# ZSLC.net
KiCad netlist of a schematic drawn in EAGLE
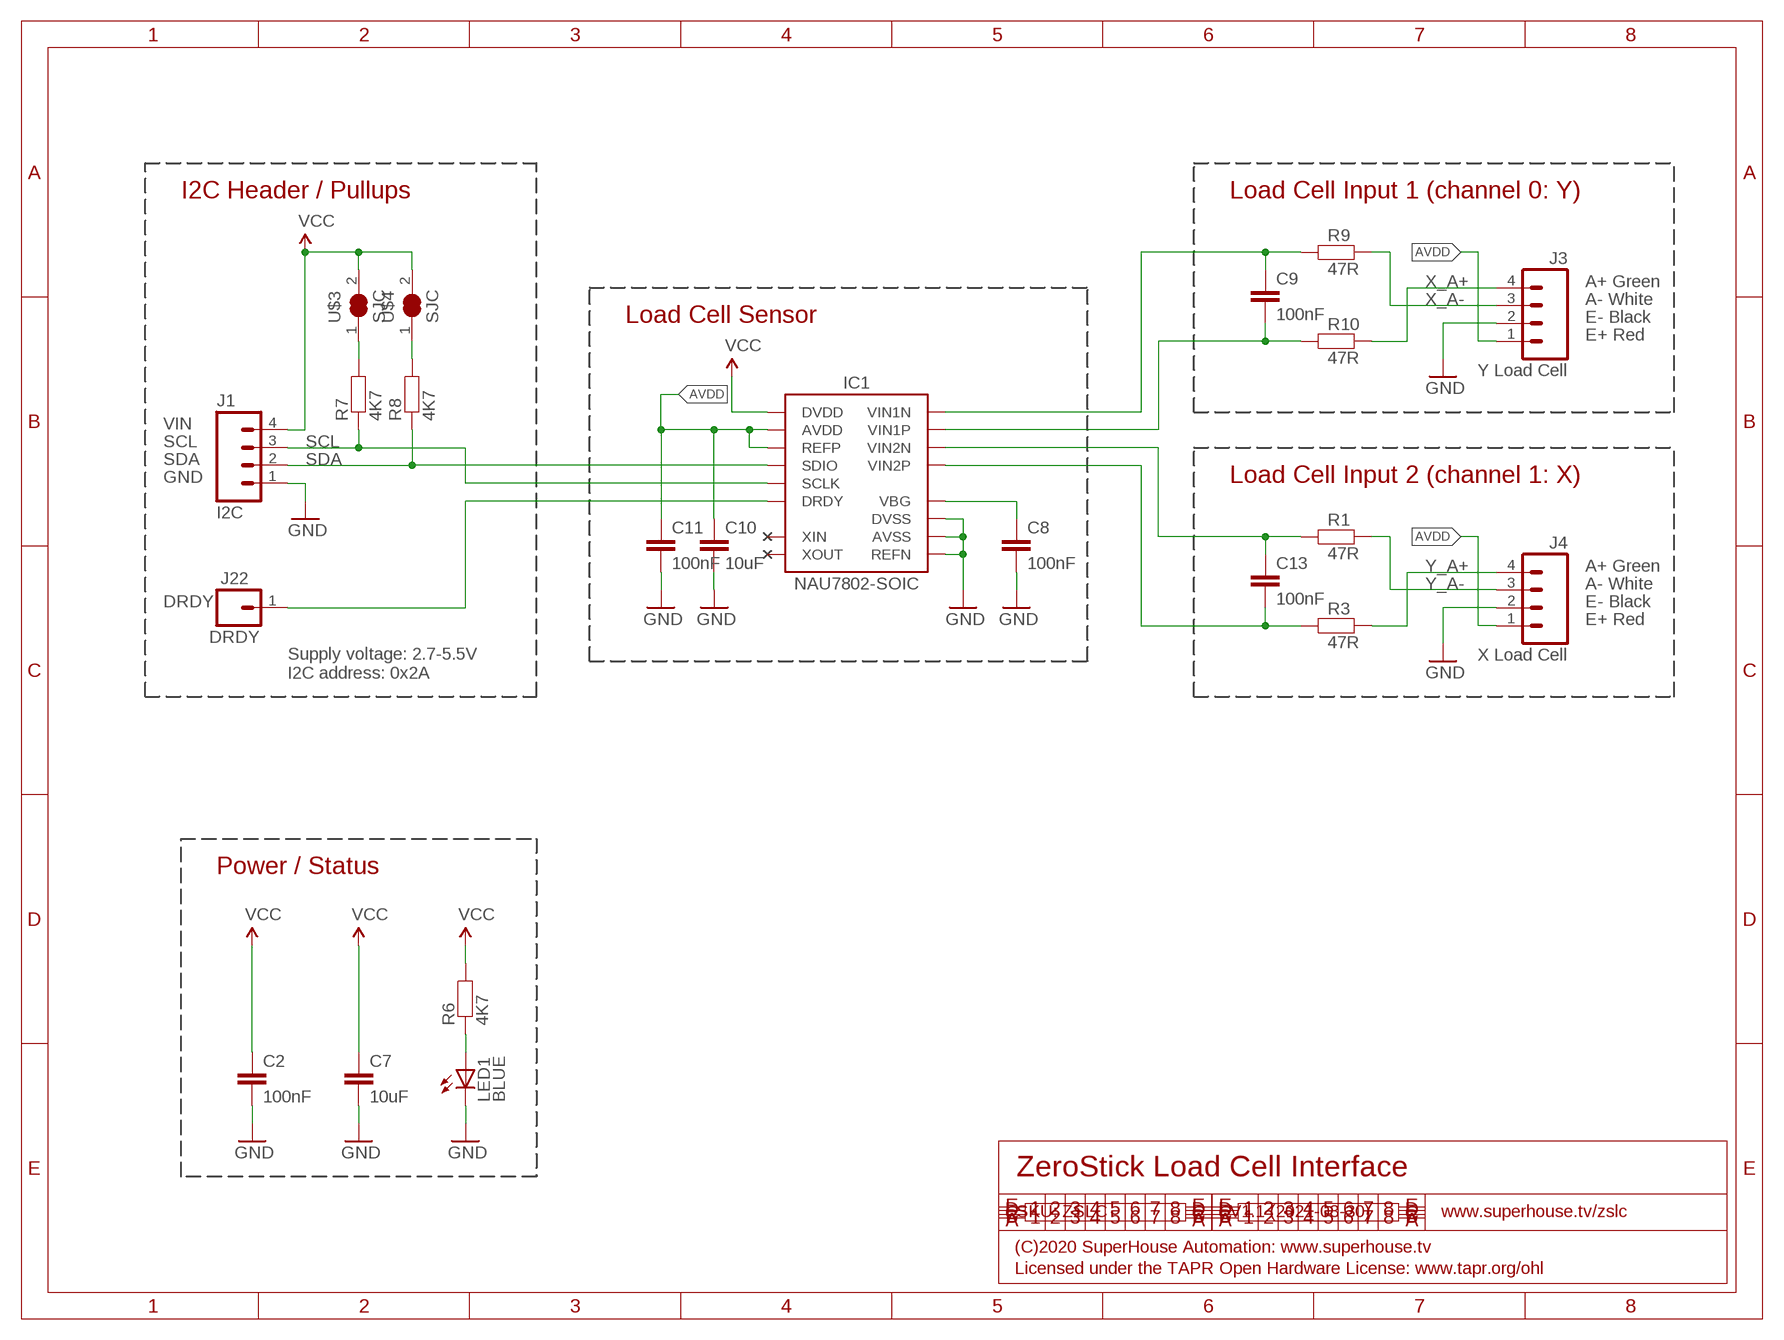
[diagram p0: schematic, sheet 1]

(export (version "E")
  (design (tool "Eeschema 10.0.6"))
  (components
    (comp (ref "C2")
      (value "100nF")
      (footprint "eagle-import:C0603")
      (libsource (lib "eagle-import") (part "CAP0603"))
    )
    (comp (ref "C7")
      (value "10uF")
      (footprint "eagle-import:C0805")
      (libsource (lib "eagle-import") (part "CAP0805"))
    )
    (comp (ref "C8")
      (value "100nF")
      (footprint "eagle-import:C0603")
      (libsource (lib "eagle-import") (part "CAP0603"))
    )
    (comp (ref "C9")
      (value "100nF")
      (footprint "eagle-import:C0603")
      (libsource (lib "eagle-import") (part "CAP0603"))
    )
    (comp (ref "C10")
      (value "10uF")
      (footprint "eagle-import:C0805")
      (libsource (lib "eagle-import") (part "CAP0805"))
    )
    (comp (ref "C11")
      (value "100nF")
      (footprint "eagle-import:C0603")
      (libsource (lib "eagle-import") (part "CAP0603"))
    )
    (comp (ref "C13")
      (value "100nF")
      (footprint "eagle-import:C0603")
      (libsource (lib "eagle-import") (part "CAP0603"))
    )
    (comp (ref "IC1")
      (value "NAU7802-SOIC")
      (footprint "eagle-import:SO16")
      (libsource (lib "eagle-import") (part "NAU7802-SOIC"))
    )
    (comp (ref "J1")
      (value "I2C")
      (footprint "eagle-import:1X04")
      (libsource (lib "eagle-import") (part "M04-PLAIN"))
    )
    (comp (ref "J3")
      (value "Y Load Cell")
      (footprint "eagle-import:1X04-1.27-PLAIN")
      (libsource (lib "eagle-import") (part "M04-1.27-PLAIN"))
    )
    (comp (ref "J4")
      (value "X Load Cell")
      (footprint "eagle-import:1X04-1.27-PLAIN")
      (libsource (lib "eagle-import") (part "M04-1.27-PLAIN"))
    )
    (comp (ref "J22")
      (value "DRDY")
      (footprint "eagle-import:1X01")
      (libsource (lib "eagle-import") (part "M01-PLAIN"))
    )
    (comp (ref "LED1")
      (value "BLUE")
      (footprint "eagle-import:LED-0603")
      (libsource (lib "eagle-import") (part "LED0603"))
    )
    (comp (ref "R1")
      (value "47R")
      (footprint "eagle-import:R0603")
      (libsource (lib "eagle-import") (part "RESISTOR0603"))
    )
    (comp (ref "R3")
      (value "47R")
      (footprint "eagle-import:R0603")
      (libsource (lib "eagle-import") (part "RESISTOR0603"))
    )
    (comp (ref "R6")
      (value "4K7")
      (footprint "eagle-import:R0603")
      (libsource (lib "eagle-import") (part "RESISTOR0603"))
    )
    (comp (ref "R7")
      (value "4K7")
      (footprint "eagle-import:R0603")
      (libsource (lib "eagle-import") (part "RESISTOR0603"))
    )
    (comp (ref "R8")
      (value "4K7")
      (footprint "eagle-import:R0603")
      (libsource (lib "eagle-import") (part "RESISTOR0603"))
    )
    (comp (ref "R9")
      (value "47R")
      (footprint "eagle-import:R0603")
      (libsource (lib "eagle-import") (part "RESISTOR0603"))
    )
    (comp (ref "R10")
      (value "47R")
      (footprint "eagle-import:R0603")
      (libsource (lib "eagle-import") (part "RESISTOR0603"))
    )
    (comp (ref "U$3")
      (value "SJC")
      (footprint "eagle-import:SJC")
      (libsource (lib "eagle-import") (part "SJC-NORMAL"))
    )
    (comp (ref "U$4")
      (value "SJC")
      (footprint "eagle-import:SJC")
      (libsource (lib "eagle-import") (part "SJC-NORMAL"))
    )
  )
  (nets
    (net (code "1") (name "/SCL") (class "Default")
      (node (ref "IC1") (pin "13") (pinfunction "SCLK_13") (pintype "bidirectional"))
      (node (ref "J1") (pin "3") (pinfunction "3_3") (pintype "passive"))
      (node (ref "R7") (pin "1") (pinfunction "1_1") (pintype "passive"))
    )
    (net (code "2") (name "/SDA") (class "Default")
      (node (ref "IC1") (pin "14") (pinfunction "SDIO_14") (pintype "bidirectional"))
      (node (ref "J1") (pin "2") (pinfunction "2_2") (pintype "passive"))
      (node (ref "R8") (pin "1") (pinfunction "1_1") (pintype "passive"))
    )
    (net (code "3") (name "/X_A+") (class "Default")
      (node (ref "J3") (pin "4") (pinfunction "4_4") (pintype "passive"))
      (node (ref "R10") (pin "2") (pinfunction "2_2") (pintype "passive"))
    )
    (net (code "4") (name "/X_A-") (class "Default")
      (node (ref "J3") (pin "3") (pinfunction "3_3") (pintype "passive"))
      (node (ref "R9") (pin "2") (pinfunction "2_2") (pintype "passive"))
    )
    (net (code "5") (name "/Y_A+") (class "Default")
      (node (ref "J4") (pin "4") (pinfunction "4_4") (pintype "passive"))
      (node (ref "R3") (pin "2") (pinfunction "2_2") (pintype "passive"))
    )
    (net (code "6") (name "/Y_A-") (class "Default")
      (node (ref "J4") (pin "3") (pinfunction "3_3") (pintype "passive"))
      (node (ref "R1") (pin "2") (pinfunction "2_2") (pintype "passive"))
    )
    (net (code "7") (name "AVDD") (class "Default")
      (node (ref "C10") (pin "1") (pinfunction "1_1") (pintype "passive"))
      (node (ref "C11") (pin "1") (pinfunction "1_1") (pintype "passive"))
      (node (ref "IC1") (pin "1") (pinfunction "REFP_1") (pintype "bidirectional"))
      (node (ref "IC1") (pin "16") (pinfunction "AVDD_16") (pintype "bidirectional"))
      (node (ref "J3") (pin "1") (pinfunction "1_1") (pintype "passive"))
      (node (ref "J4") (pin "1") (pinfunction "1_1") (pintype "passive"))
    )
    (net (code "8") (name "GND") (class "Default")
      (node (ref "C10") (pin "2") (pinfunction "2_2") (pintype "passive"))
      (node (ref "C11") (pin "2") (pinfunction "2_2") (pintype "passive"))
      (node (ref "C2") (pin "2") (pinfunction "2_2") (pintype "passive"))
      (node (ref "C7") (pin "2") (pinfunction "2_2") (pintype "passive"))
      (node (ref "C8") (pin "2") (pinfunction "2_2") (pintype "passive"))
      (node (ref "IC1") (pin "7") (pinfunction "REFN_7") (pintype "bidirectional"))
      (node (ref "IC1") (pin "8") (pinfunction "AVSS_8") (pintype "bidirectional"))
      (node (ref "IC1") (pin "9") (pinfunction "DVSS_9") (pintype "bidirectional"))
      (node (ref "J1") (pin "1") (pinfunction "1_1") (pintype "passive"))
      (node (ref "J3") (pin "2") (pinfunction "2_2") (pintype "passive"))
      (node (ref "J4") (pin "2") (pinfunction "2_2") (pintype "passive"))
      (node (ref "LED1") (pin "C") (pinfunction "C_C") (pintype "passive"))
    )
    (net (code "9") (name "Net-(IC1-DRDY)") (class "Default")
      (node (ref "IC1") (pin "12") (pinfunction "DRDY_12") (pintype "bidirectional"))
      (node (ref "J22") (pin "1") (pinfunction "1_1") (pintype "passive"))
    )
    (net (code "10") (name "Net-(IC1-VBG)") (class "Default")
      (node (ref "C8") (pin "1") (pinfunction "1_1") (pintype "passive"))
      (node (ref "IC1") (pin "6") (pinfunction "VBG_6") (pintype "bidirectional"))
    )
    (net (code "11") (name "Net-(IC1-VIN1N)") (class "Default")
      (node (ref "C9") (pin "1") (pinfunction "1_1") (pintype "passive"))
      (node (ref "IC1") (pin "2") (pinfunction "VIN1N_2") (pintype "bidirectional"))
      (node (ref "R9") (pin "1") (pinfunction "1_1") (pintype "passive"))
    )
    (net (code "12") (name "Net-(IC1-VIN1P)") (class "Default")
      (node (ref "C9") (pin "2") (pinfunction "2_2") (pintype "passive"))
      (node (ref "IC1") (pin "3") (pinfunction "VIN1P_3") (pintype "bidirectional"))
      (node (ref "R10") (pin "1") (pinfunction "1_1") (pintype "passive"))
    )
    (net (code "13") (name "Net-(IC1-VIN2N)") (class "Default")
      (node (ref "C13") (pin "1") (pinfunction "1_1") (pintype "passive"))
      (node (ref "IC1") (pin "4") (pinfunction "VIN2N_4") (pintype "bidirectional"))
      (node (ref "R1") (pin "1") (pinfunction "1_1") (pintype "passive"))
    )
    (net (code "14") (name "Net-(IC1-VIN2P)") (class "Default")
      (node (ref "C13") (pin "2") (pinfunction "2_2") (pintype "passive"))
      (node (ref "IC1") (pin "5") (pinfunction "VIN2P_5") (pintype "bidirectional"))
      (node (ref "R3") (pin "1") (pinfunction "1_1") (pintype "passive"))
    )
    (net (code "15") (name "Net-(LED1-PadA)") (class "Default")
      (node (ref "LED1") (pin "A") (pinfunction "A_A") (pintype "passive"))
      (node (ref "R6") (pin "1") (pinfunction "1_1") (pintype "passive"))
    )
    (net (code "16") (name "Net-(R7-Pad2)") (class "Default")
      (node (ref "R7") (pin "2") (pinfunction "2_2") (pintype "passive"))
      (node (ref "U$3") (pin "1") (pinfunction "1_1") (pintype "passive"))
    )
    (net (code "17") (name "Net-(R8-Pad2)") (class "Default")
      (node (ref "R8") (pin "2") (pinfunction "2_2") (pintype "passive"))
      (node (ref "U$4") (pin "1") (pinfunction "1_1") (pintype "passive"))
    )
    (net (code "18") (name "VCC") (class "Default")
      (node (ref "C2") (pin "1") (pinfunction "1_1") (pintype "passive"))
      (node (ref "C7") (pin "1") (pinfunction "1_1") (pintype "passive"))
      (node (ref "IC1") (pin "15") (pinfunction "DVDD_15") (pintype "bidirectional"))
      (node (ref "J1") (pin "4") (pinfunction "4_4") (pintype "passive"))
      (node (ref "R6") (pin "2") (pinfunction "2_2") (pintype "passive"))
      (node (ref "U$3") (pin "2") (pinfunction "2_2") (pintype "passive"))
      (node (ref "U$4") (pin "2") (pinfunction "2_2") (pintype "passive"))
    )
    (net (code "19") (name "unconnected-(IC1-XIN-Pad10)") (class "Default")
      (node (ref "IC1") (pin "10") (pinfunction "XIN_10") (pintype "bidirectional"))
    )
    (net (code "20") (name "unconnected-(IC1-XOUT-Pad11)") (class "Default")
      (node (ref "IC1") (pin "11") (pinfunction "XOUT_11") (pintype "bidirectional"))
    )
  )
)
